# ZippyLighthouseCircuit_v17.net
KiCad netlist of a schematic drawn in EAGLE
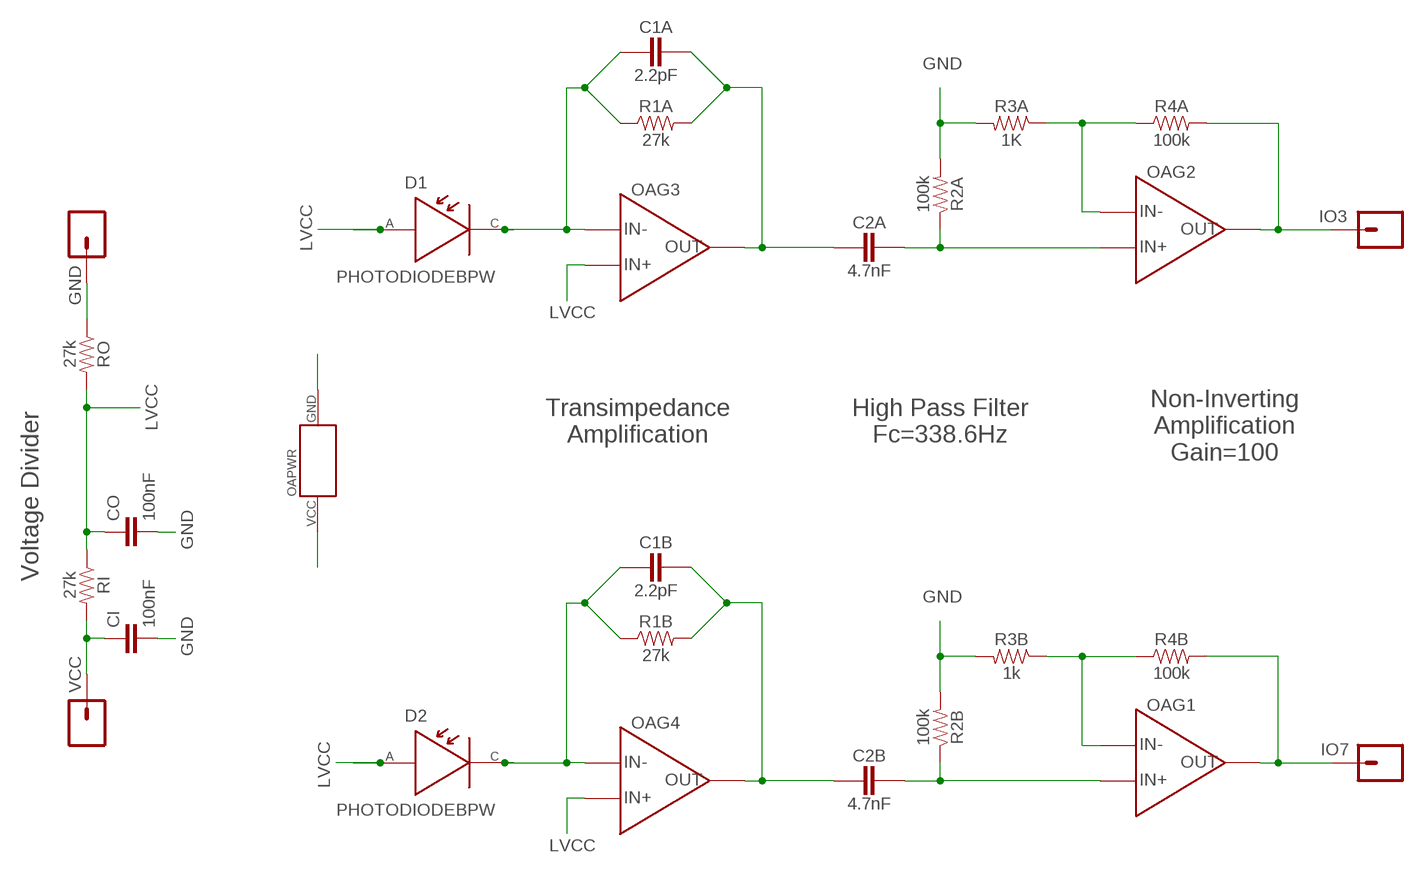
[diagram p0: schematic, sheet 1]

(export (version "E")
  (design (tool "Eeschema 10.0.6"))
  (components
    (comp (ref "C1A")
      (value "2.2pF")
      (footprint "eagle-import:PASSIVE-0603")
      (libsource (lib "eagle-import") (part "CAPACITOR"))
    )
    (comp (ref "C1B")
      (value "2.2pF")
      (footprint "eagle-import:PASSIVE-0603")
      (libsource (lib "eagle-import") (part "CAPACITOR"))
    )
    (comp (ref "C2A")
      (value "4.7nF")
      (footprint "eagle-import:PASSIVE-0603")
      (libsource (lib "eagle-import") (part "CAPACITOR"))
    )
    (comp (ref "C2B")
      (value "4.7nF")
      (footprint "eagle-import:PASSIVE-0603")
      (libsource (lib "eagle-import") (part "CAPACITOR"))
    )
    (comp (ref "CI")
      (value "100nF")
      (footprint "eagle-import:0603")
      (libsource (lib "eagle-import") (part "4.7PF-0603-50V-5%"))
    )
    (comp (ref "CO")
      (value "100nF")
      (footprint "eagle-import:0603")
      (libsource (lib "eagle-import") (part "4.7PF-0603-50V-5%"))
    )
    (comp (ref "D1")
      (value "PHOTODIODEBPW")
      (footprint "eagle-import:BPW34_BP104_SMD")
      (libsource (lib "eagle-import") (part "PHOTODIODEBPW"))
    )
    (comp (ref "D2")
      (value "PHOTODIODEBPW")
      (footprint "eagle-import:BPW34_BP104_SMD")
      (libsource (lib "eagle-import") (part "PHOTODIODEBPW"))
    )
    (comp (ref "GND")
      (value "CONN_01PTH_NO_SILK_YES_STOP")
      (footprint "eagle-import:1X01_NO_SILK")
      (libsource (lib "eagle-import") (part "CONN_01PTH_NO_SILK_YES_STOP"))
    )
    (comp (ref "IO3")
      (value "CONN_01PTH_NO_SILK_YES_STOP")
      (footprint "eagle-import:1X01_NO_SILK")
      (libsource (lib "eagle-import") (part "CONN_01PTH_NO_SILK_YES_STOP"))
    )
    (comp (ref "IO7")
      (value "CONN_01PTH_NO_SILK_YES_STOP")
      (footprint "eagle-import:1X01_NO_SILK")
      (libsource (lib "eagle-import") (part "CONN_01PTH_NO_SILK_YES_STOP"))
    )
    (comp (ref "OA")
      (value "TLV2464IDM")
      (footprint "eagle-import:D14-M")
      (libsource (lib "eagle-import") (part "TLV2464IDM"))
    )
    (comp (ref "R1A")
      (value "27k")
      (footprint "eagle-import:PASSIVE-0603")
      (libsource (lib "eagle-import") (part "RESISTOR"))
    )
    (comp (ref "R1B")
      (value "27k")
      (footprint "eagle-import:PASSIVE-0603")
      (libsource (lib "eagle-import") (part "RESISTOR"))
    )
    (comp (ref "R2A")
      (value "100k")
      (footprint "eagle-import:PASSIVE-0603")
      (libsource (lib "eagle-import") (part "RESISTOR"))
    )
    (comp (ref "R2B")
      (value "100k")
      (footprint "eagle-import:PASSIVE-0603")
      (libsource (lib "eagle-import") (part "RESISTOR"))
    )
    (comp (ref "R3A")
      (value "1K")
      (footprint "eagle-import:PASSIVE-0603")
      (libsource (lib "eagle-import") (part "RESISTOR"))
    )
    (comp (ref "R3B")
      (value "1k")
      (footprint "eagle-import:PASSIVE-0603")
      (libsource (lib "eagle-import") (part "RESISTOR"))
    )
    (comp (ref "R4A")
      (value "100k")
      (footprint "eagle-import:PASSIVE-0603")
      (libsource (lib "eagle-import") (part "RESISTOR"))
    )
    (comp (ref "R4B")
      (value "100k")
      (footprint "eagle-import:PASSIVE-0603")
      (libsource (lib "eagle-import") (part "RESISTOR"))
    )
    (comp (ref "RI")
      (value "27k")
      (footprint "eagle-import:0603")
      (libsource (lib "eagle-import") (part "100KOHM-0603-1/10W-1%"))
    )
    (comp (ref "RO")
      (value "27k")
      (footprint "eagle-import:0603")
      (libsource (lib "eagle-import") (part "100KOHM-0603-1/10W-1%"))
    )
    (comp (ref "VCC")
      (value "CONN_01PTH_NO_SILK_YES_STOP")
      (footprint "eagle-import:1X01_NO_SILK")
      (libsource (lib "eagle-import") (part "CONN_01PTH_NO_SILK_YES_STOP"))
    )
  )
  (nets
    (net (code "1") (name "/GND") (class "Default")
      (node (ref "CI") (pin "2") (pinfunction "2_2") (pintype "passive"))
      (node (ref "CO") (pin "2") (pinfunction "2_2") (pintype "passive"))
      (node (ref "GND") (pin "1") (pinfunction "1_1") (pintype "passive"))
      (node (ref "OA") (pin "11") (pinfunction "GND_11") (pintype "bidirectional"))
      (node (ref "R2A") (pin "2") (pinfunction "2_2") (pintype "passive"))
      (node (ref "R2B") (pin "2") (pinfunction "2_2") (pintype "passive"))
      (node (ref "R3A") (pin "2") (pinfunction "2_2") (pintype "passive"))
      (node (ref "R3B") (pin "2") (pinfunction "2_2") (pintype "passive"))
      (node (ref "RO") (pin "1") (pinfunction "1_1") (pintype "passive"))
    )
    (net (code "2") (name "/IO3") (class "Default")
      (node (ref "IO3") (pin "1") (pinfunction "1_1") (pintype "passive"))
      (node (ref "OA") (pin "7") (pinfunction "OUT_7") (pintype "bidirectional"))
      (node (ref "R4A") (pin "2") (pinfunction "2_2") (pintype "passive"))
    )
    (net (code "3") (name "/IO7") (class "Default")
      (node (ref "IO7") (pin "1") (pinfunction "1_1") (pintype "passive"))
      (node (ref "OA") (pin "1") (pinfunction "OUT_1") (pintype "bidirectional"))
      (node (ref "R4B") (pin "2") (pinfunction "2_2") (pintype "passive"))
    )
    (net (code "4") (name "/LVCC") (class "Default")
      (node (ref "CO") (pin "1") (pinfunction "1_1") (pintype "passive"))
      (node (ref "D1") (pin "ANODE") (pinfunction "ANODE_ANODE") (pintype "bidirectional"))
      (node (ref "D2") (pin "ANODE") (pinfunction "ANODE_ANODE") (pintype "bidirectional"))
      (node (ref "OA") (pin "10") (pinfunction "IN+_10") (pintype "bidirectional"))
      (node (ref "OA") (pin "12") (pinfunction "IN+_12") (pintype "bidirectional"))
      (node (ref "RI") (pin "1") (pinfunction "1_1") (pintype "passive"))
      (node (ref "RO") (pin "2") (pinfunction "2_2") (pintype "passive"))
    )
    (net (code "5") (name "/VCC") (class "Default")
      (node (ref "CI") (pin "1") (pinfunction "1_1") (pintype "passive"))
      (node (ref "OA") (pin "4") (pinfunction "VCC_4") (pintype "bidirectional"))
      (node (ref "RI") (pin "2") (pinfunction "2_2") (pintype "passive"))
      (node (ref "VCC") (pin "1") (pinfunction "1_1") (pintype "passive"))
    )
    (net (code "6") (name "Net-(OAA-IN+)") (class "Default")
      (node (ref "C2B") (pin "2") (pinfunction "2_2") (pintype "passive"))
      (node (ref "OA") (pin "3") (pinfunction "IN+_3") (pintype "bidirectional"))
      (node (ref "R2B") (pin "1") (pinfunction "1_1") (pintype "passive"))
    )
    (net (code "7") (name "Net-(OAA-IN-)") (class "Default")
      (node (ref "OA") (pin "2") (pinfunction "IN-_2") (pintype "bidirectional"))
      (node (ref "R3B") (pin "1") (pinfunction "1_1") (pintype "passive"))
      (node (ref "R4B") (pin "1") (pinfunction "1_1") (pintype "passive"))
    )
    (net (code "8") (name "Net-(OAB-IN+)") (class "Default")
      (node (ref "C2A") (pin "2") (pinfunction "2_2") (pintype "passive"))
      (node (ref "OA") (pin "5") (pinfunction "IN+_5") (pintype "bidirectional"))
      (node (ref "R2A") (pin "1") (pinfunction "1_1") (pintype "passive"))
    )
    (net (code "9") (name "Net-(OAB-IN-)") (class "Default")
      (node (ref "OA") (pin "6") (pinfunction "IN-_6") (pintype "bidirectional"))
      (node (ref "R3A") (pin "1") (pinfunction "1_1") (pintype "passive"))
      (node (ref "R4A") (pin "1") (pinfunction "1_1") (pintype "passive"))
    )
    (net (code "10") (name "Net-(OAC-IN-)") (class "Default")
      (node (ref "C1A") (pin "1") (pinfunction "1_1") (pintype "passive"))
      (node (ref "D1") (pin "CATHODE") (pinfunction "CATHODE_CATHODE") (pintype "bidirectional"))
      (node (ref "OA") (pin "9") (pinfunction "IN-_9") (pintype "bidirectional"))
      (node (ref "R1A") (pin "1") (pinfunction "1_1") (pintype "passive"))
    )
    (net (code "11") (name "Net-(OAC-OUT)") (class "Default")
      (node (ref "C1A") (pin "2") (pinfunction "2_2") (pintype "passive"))
      (node (ref "C2A") (pin "1") (pinfunction "1_1") (pintype "passive"))
      (node (ref "OA") (pin "8") (pinfunction "OUT_8") (pintype "bidirectional"))
      (node (ref "R1A") (pin "2") (pinfunction "2_2") (pintype "passive"))
    )
    (net (code "12") (name "Net-(OAD-IN-)") (class "Default")
      (node (ref "C1B") (pin "1") (pinfunction "1_1") (pintype "passive"))
      (node (ref "D2") (pin "CATHODE") (pinfunction "CATHODE_CATHODE") (pintype "bidirectional"))
      (node (ref "OA") (pin "13") (pinfunction "IN-_13") (pintype "bidirectional"))
      (node (ref "R1B") (pin "1") (pinfunction "1_1") (pintype "passive"))
    )
    (net (code "13") (name "Net-(OAD-OUT)") (class "Default")
      (node (ref "C1B") (pin "2") (pinfunction "2_2") (pintype "passive"))
      (node (ref "C2B") (pin "1") (pinfunction "1_1") (pintype "passive"))
      (node (ref "OA") (pin "14") (pinfunction "OUT_14") (pintype "bidirectional"))
      (node (ref "R1B") (pin "2") (pinfunction "2_2") (pintype "passive"))
    )
  )
)
